# RS485.net
KiCad netlist of a schematic drawn in Altium Designer
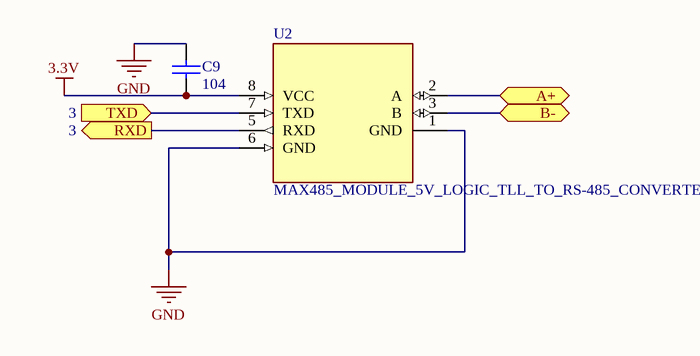
[diagram p0: RS485.SchDoc]

(export (version "E")
  (design (tool "Eeschema 10.0.6"))
  (components
    (comp (ref "C9")
      (value "104")
      (footprint "tu gom")
      (description "Cắm")
      (libsource (lib "Altium_Lib_by_KhueNguyenCreator") (part "Tu gom 104 50V"))
    )
    (comp (ref "U2")
      (value "MAX485_MODULE_5V_LOGIC_TLL_TO_RS-485_CONVERTER")
      (footprint "MODULE_MAX485_MODULE_5V_LOGIC_TLL_TO_RS-485_CONVERTER")
      (description "5V MAX485 TTL To RS485 Converter Module Board for Arduino")
      (fields
        (field (name "MP") "MAX485 Module 5V logic TLL to RS-485 converter")
        (field (name "MF") "e-Gizmo Mechatronix Central")
      )
      (libsource (lib "MAX485_MODULE_5V_LOGIC_TLL_TO_RS-485_CONVERTER") (part "MAX485_MODULE_5V_LOGIC_TLL_TO_RS-485_CONVERTER"))
    )
  )
  (nets
    (net (code "1") (name "/A+") (class "Default")
      (node (ref "U2") (pin "2") (pinfunction "A_2") (pintype "bidirectional"))
    )
    (net (code "2") (name "/B-") (class "Default")
      (node (ref "U2") (pin "3") (pinfunction "B_3") (pintype "bidirectional"))
    )
    (net (code "3") (name "/RXD") (class "Default")
      (node (ref "U2") (pin "5") (pinfunction "RXD_5") (pintype "output"))
    )
    (net (code "4") (name "/TXD") (class "Default")
      (node (ref "U2") (pin "7") (pinfunction "TXD_7") (pintype "input"))
    )
    (net (code "5") (name "3.3V") (class "Default")
      (node (ref "C9") (pin "2") (pinfunction "2_2") (pintype "passive"))
      (node (ref "U2") (pin "8") (pinfunction "VCC_8") (pintype "input"))
    )
    (net (code "6") (name "GND") (class "Default")
      (node (ref "C9") (pin "1") (pinfunction "1_1") (pintype "passive"))
      (node (ref "U2") (pin "1") (pinfunction "GND_1") (pintype "power_in"))
      (node (ref "U2") (pin "6") (pinfunction "GND_6") (pintype "input"))
    )
  )
)
